# AudioAmp_TLC272.net
KiCad netlist of a schematic drawn in EAGLE
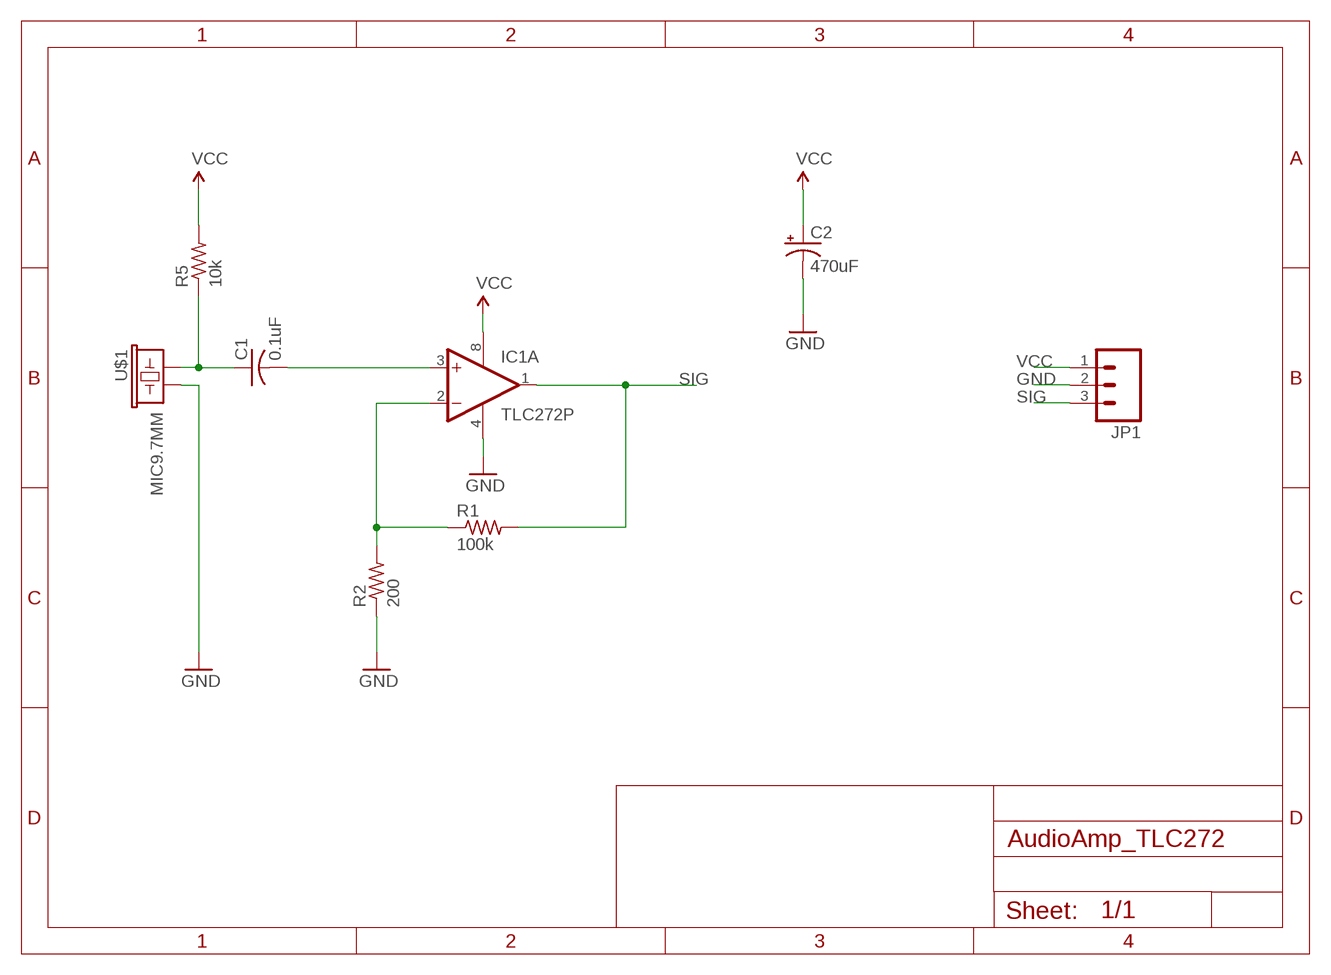
[diagram p0: schematic, sheet 1]

(export (version "E")
  (design (tool "Eeschema 10.0.6"))
  (components
    (comp (ref "C1")
      (value "0.1uF")
      (footprint "eagle-import:C025-025X050")
      (libsource (lib "eagle-import") (part "C-US025-025X050"))
    )
    (comp (ref "C2")
      (value "470uF")
      (footprint "eagle-import:E2,5-7")
      (libsource (lib "eagle-import") (part "CPOL-USE2.5-7"))
    )
    (comp (ref "IC1")
      (value "TLC272P")
      (footprint "eagle-import:DIL08")
      (libsource (lib "eagle-import") (part "TLC272P"))
    )
    (comp (ref "JP1")
      (value "M03PTH")
      (footprint "eagle-import:1X03")
      (libsource (lib "eagle-import") (part "M03PTH"))
    )
    (comp (ref "R1")
      (value "100k")
      (footprint "eagle-import:0207_10")
      (libsource (lib "eagle-import") (part "R-US_0207/10"))
    )
    (comp (ref "R2")
      (value "200")
      (footprint "eagle-import:0207_10")
      (libsource (lib "eagle-import") (part "R-US_0207/10"))
    )
    (comp (ref "R5")
      (value "10k")
      (footprint "eagle-import:0207_10")
      (libsource (lib "eagle-import") (part "R-US_0207/10"))
    )
    (comp (ref "U$1")
      (value "MIC9.7MM")
      (footprint "eagle-import:MIC-9.7MM")
      (libsource (lib "eagle-import") (part "MIC9.7MM"))
    )
  )
  (nets
    (net (code "1") (name "/SIG") (class "Default")
      (node (ref "IC1") (pin "1") (pinfunction "OUT_1") (pintype "output"))
      (node (ref "JP1") (pin "3") (pinfunction "3_3") (pintype "passive"))
      (node (ref "R1") (pin "2") (pinfunction "2_2") (pintype "passive"))
    )
    (net (code "2") (name "GND") (class "Default")
      (node (ref "C2") (pin "-") (pinfunction "-_-") (pintype "passive"))
      (node (ref "IC1") (pin "4") (pinfunction "V-_4") (pintype "power_in"))
      (node (ref "JP1") (pin "2") (pinfunction "2_2") (pintype "passive"))
      (node (ref "R2") (pin "1") (pinfunction "1_1") (pintype "passive"))
      (node (ref "U$1") (pin "2") (pinfunction "2_2") (pintype "passive"))
    )
    (net (code "3") (name "Net-(C1-Pad1)") (class "Default")
      (node (ref "C1") (pin "1") (pinfunction "1_1") (pintype "passive"))
      (node (ref "R5") (pin "1") (pinfunction "1_1") (pintype "passive"))
      (node (ref "U$1") (pin "1") (pinfunction "1_1") (pintype "passive"))
    )
    (net (code "4") (name "Net-(IC1A-+IN)") (class "Default")
      (node (ref "C1") (pin "2") (pinfunction "2_2") (pintype "passive"))
      (node (ref "IC1") (pin "3") (pinfunction "+IN_3") (pintype "input"))
    )
    (net (code "5") (name "Net-(IC1A--IN)") (class "Default")
      (node (ref "IC1") (pin "2") (pinfunction "-IN_2") (pintype "input"))
      (node (ref "R1") (pin "1") (pinfunction "1_1") (pintype "passive"))
      (node (ref "R2") (pin "2") (pinfunction "2_2") (pintype "passive"))
    )
    (net (code "6") (name "VCC") (class "Default")
      (node (ref "C2") (pin "+") (pinfunction "+_+") (pintype "passive"))
      (node (ref "IC1") (pin "8") (pinfunction "V+_8") (pintype "power_in"))
      (node (ref "JP1") (pin "1") (pinfunction "1_1") (pintype "passive"))
      (node (ref "R5") (pin "2") (pinfunction "2_2") (pintype "passive"))
    )
  )
)
